# fpga1.net
KiCad netlist of a schematic drawn in Altium Designer
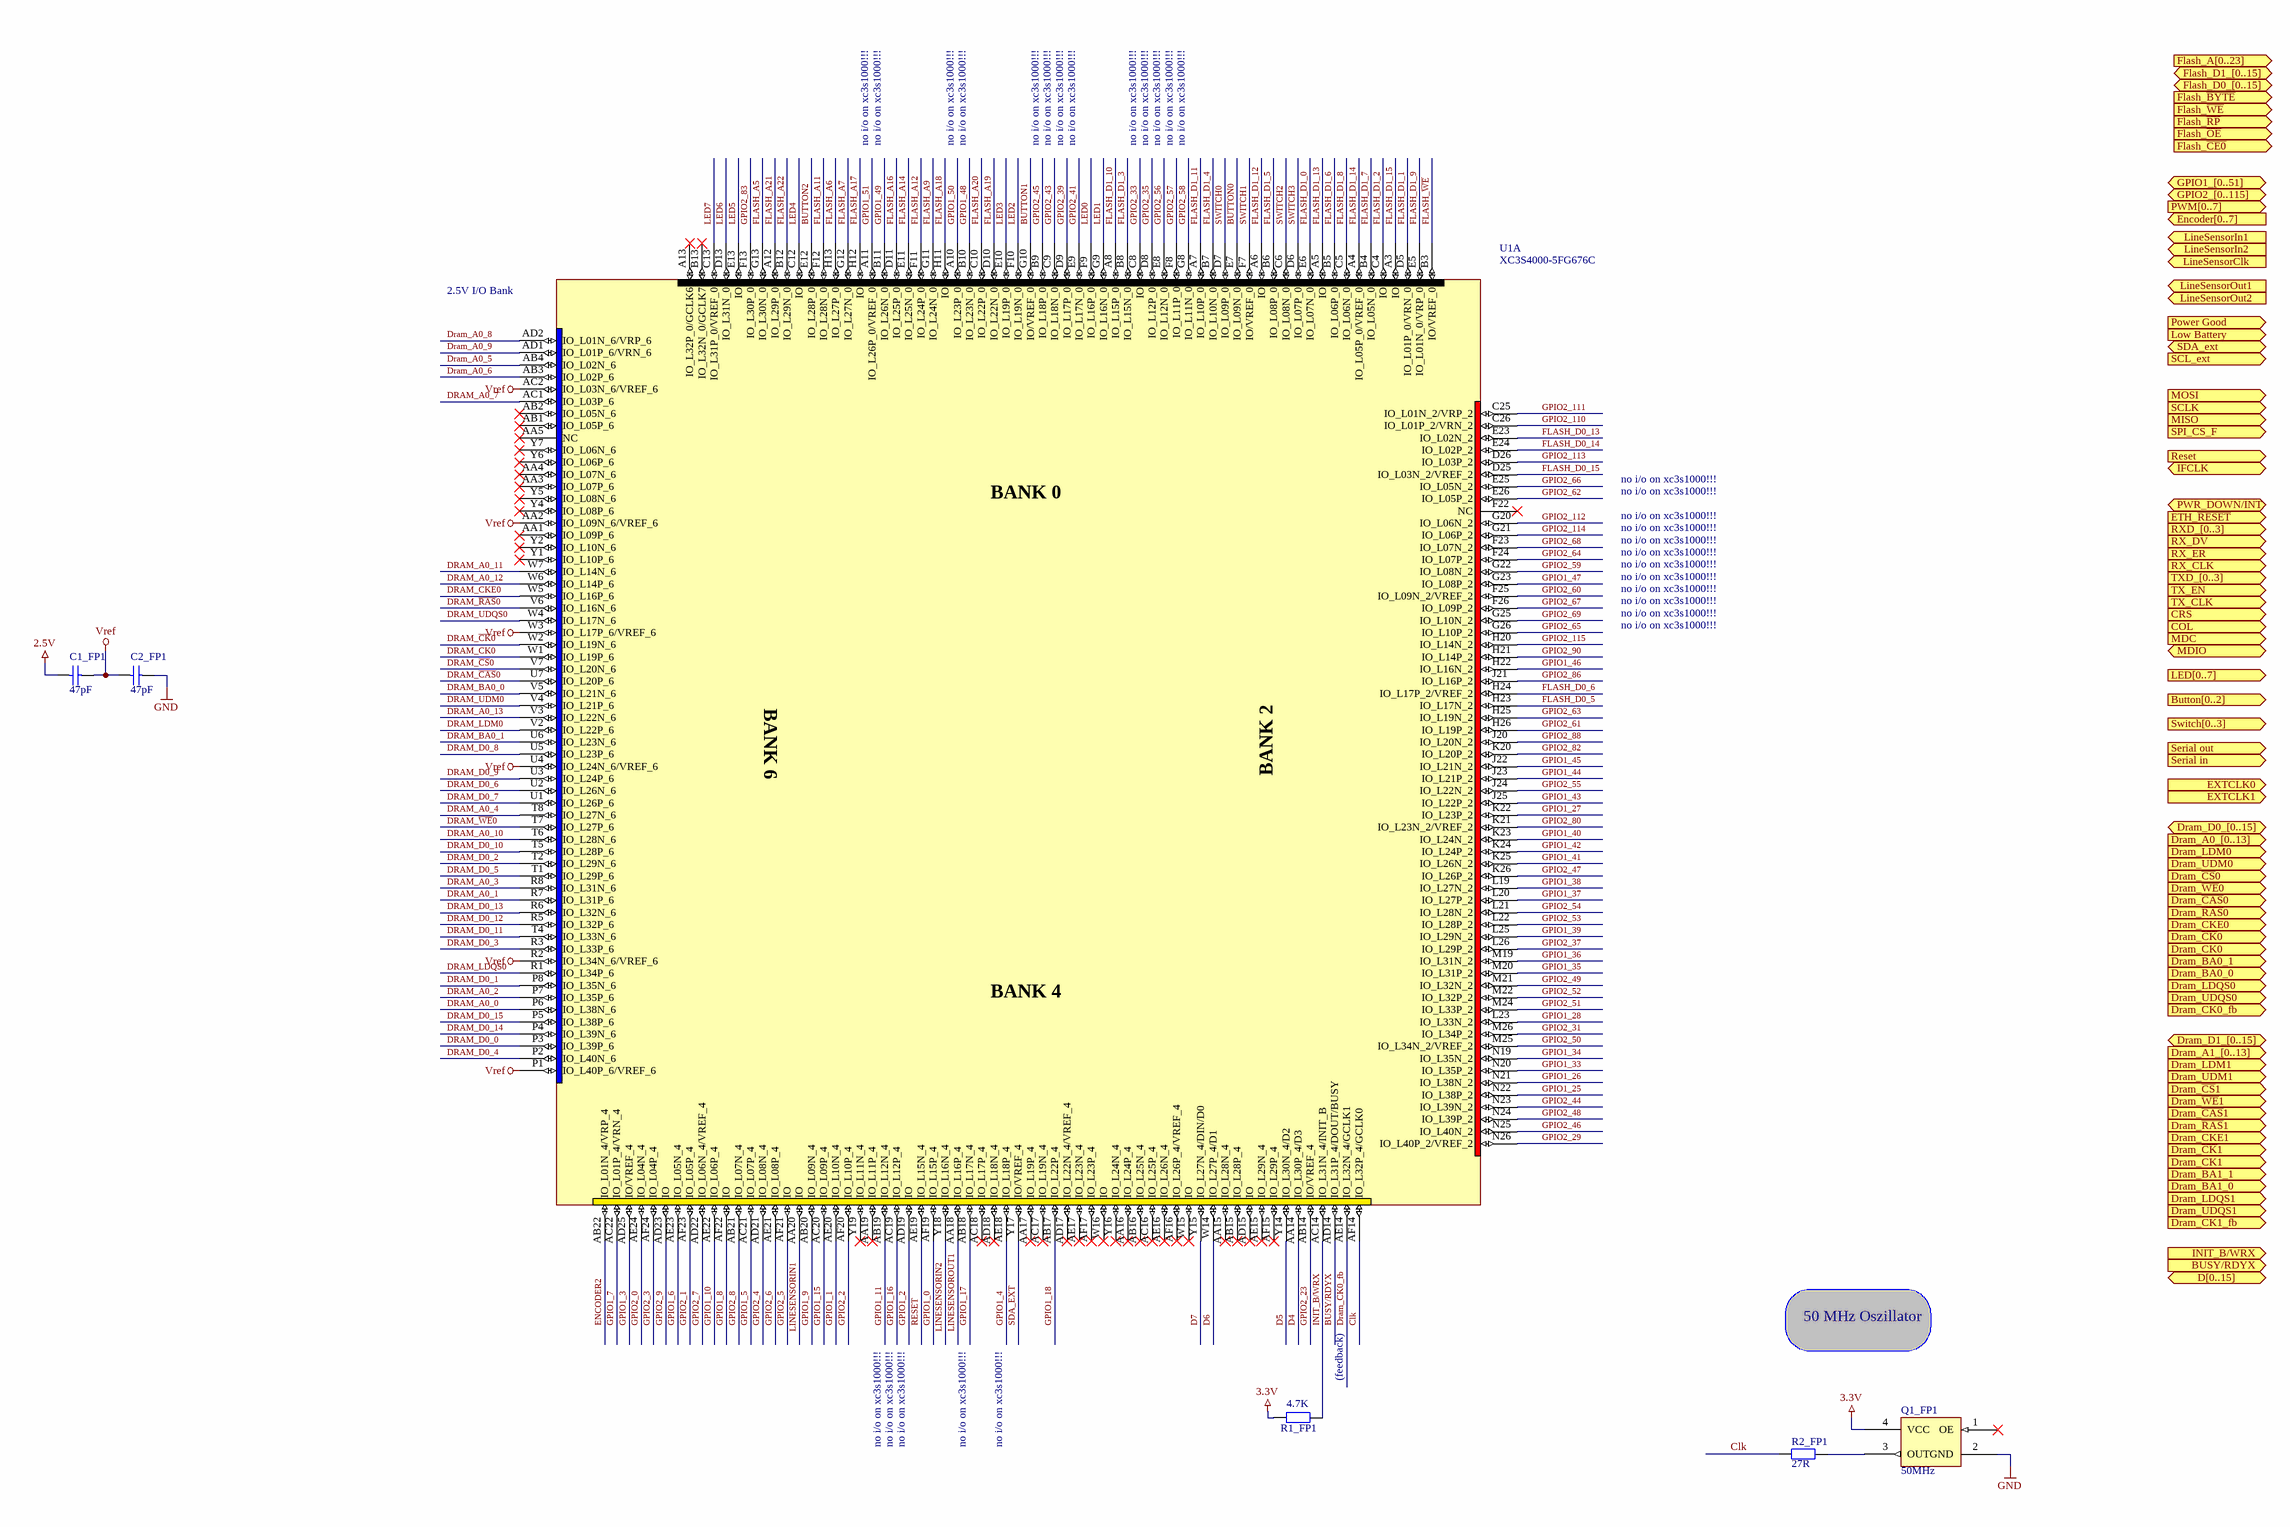
[diagram p0: fpga1.SchDoc]

(export (version "E")
  (design (tool "Eeschema 10.0.6"))
  (components
    (comp (ref "C1_FP1")
      (value "47pF")
      (footprint "0402")
      (description "Capacitor")
      (fields
        (field (name "MANUFACTURER") "Murata")
        (field (name "PART NUMBER") "GRM1555C1H470JZ01D")
        (field (name "PUBLISHER") "Altium Limited")
      )
      (libsource (lib "Miscellaneous Devices") (part "Cap"))
    )
    (comp (ref "C2_FP1")
      (value "47pF")
      (footprint "0402")
      (description "Capacitor")
      (fields
        (field (name "MANUFACTURER") "Murata")
        (field (name "PART NUMBER") "GRM1555C1H470JZ01D")
        (field (name "PUBLISHER") "Altium Limited")
      )
      (libsource (lib "Miscellaneous Devices") (part "Cap"))
    )
    (comp (ref "Q1_FP1")
      (value "50MHz")
      (footprint "SMD-VX3E")
      (description "TTL Quarz Oszillator")
      (fields (field (name "MANUFACTURER") "Jauch") (field (name "PART NUMBER") "VX3MH-5000"))
      (libsource (lib "CoolARM-Kit") (part "QUARZ_OSZI_SMD"))
    )
    (comp (ref "R1_FP1")
      (value "4.7K")
      (footprint "0402")
      (description "Resistor")
      (fields
        (field (name "MANUFACTURER") "PHYCOMP")
        (field (name "PART NUMBER") "232270674702")
        (field (name "PUBLISHER") "Altium Limited")
      )
      (libsource (lib "Miscellaneous Devices") (part "Res2"))
    )
    (comp (ref "R2_FP1")
      (value "27R")
      (footprint "0402")
      (description "Resistor")
      (fields
        (field (name "MANUFACTURER") "PHYCOMP")
        (field (name "PART NUMBER") "232270672709")
        (field (name "PUBLISHER") "Altium Limited")
      )
      (libsource (lib "Miscellaneous Devices") (part "Res2"))
    )
    (comp (ref "U1")
      (value "XC3S4000-5FG676C")
      (footprint "FG676")
      (description "Spartan-3 1.2V FPGA, 487 User I/Os, 676-ball FBGA, High Performance, Commercial Grade")
      (fields (field (name "MANUFACTURER") "Xilinx") (field (name "PUBLISHER") "Altium Limited"))
      (libsource (lib "gecko3-user") (part "XC3S1500-5FG676C"))
    )
  )
  (nets
    (net (code "228") (name "/BUSY{slash}RDYX") (class "Default")
      (node (ref "U1") (pin "AD14") (pinfunction "IO_L31P_4/DOUT/BUSY_AD14") (pintype "bidirectional"))
    )
    (net (code "229") (name "/BUTTON0") (class "Default")
      (node (ref "U1") (pin "E7") (pinfunction "IO_L09N_0_E7") (pintype "bidirectional"))
    )
    (net (code "230") (name "/BUTTON1") (class "Default")
      (node (ref "U1") (pin "G10") (pinfunction "IO/VREF_0_G10") (pintype "bidirectional"))
    )
    (net (code "231") (name "/BUTTON2") (class "Default")
      (node (ref "U1") (pin "E12") (pinfunction "IO_L28P_0_E12") (pintype "bidirectional"))
    )
    (net (code "235") (name "/Clk") (class "Default")
      (node (ref "R2_FP1") (pin "1") (pinfunction "1_1") (pintype "passive"))
      (node (ref "U1") (pin "AF14") (pinfunction "IO_L32P_4/GCLK0_AF14") (pintype "bidirectional"))
    )
    (net (code "236") (name "/D4") (class "Default")
      (node (ref "U1") (pin "AA14") (pinfunction "IO_L30P_4/D3_AA14") (pintype "bidirectional"))
    )
    (net (code "237") (name "/D5") (class "Default")
      (node (ref "U1") (pin "Y14") (pinfunction "IO_L30N_4/D2_Y14") (pintype "bidirectional"))
    )
    (net (code "238") (name "/D6") (class "Default")
      (node (ref "U1") (pin "W14") (pinfunction "IO_L27P_4/D1_W14") (pintype "bidirectional"))
    )
    (net (code "239") (name "/D7") (class "Default")
      (node (ref "U1") (pin "Y15") (pinfunction "IO_L27N_4/DIN/D0_Y15") (pintype "bidirectional"))
    )
    (net (code "240") (name "/DRAM_A0_0") (class "Default")
      (node (ref "U1") (pin "P6") (pinfunction "IO_L38N_6_P6") (pintype "bidirectional"))
    )
    (net (code "241") (name "/DRAM_A0_1") (class "Default")
      (node (ref "U1") (pin "R7") (pinfunction "IO_L31P_6_R7") (pintype "bidirectional"))
    )
    (net (code "242") (name "/DRAM_A0_2") (class "Default")
      (node (ref "U1") (pin "P7") (pinfunction "IO_L35P_6_P7") (pintype "bidirectional"))
    )
    (net (code "243") (name "/DRAM_A0_3") (class "Default")
      (node (ref "U1") (pin "R8") (pinfunction "IO_L31N_6_R8") (pintype "bidirectional"))
    )
    (net (code "244") (name "/DRAM_A0_4") (class "Default")
      (node (ref "U1") (pin "T8") (pinfunction "IO_L27N_6_T8") (pintype "bidirectional"))
    )
    (net (code "245") (name "/DRAM_A0_7") (class "Default")
      (node (ref "U1") (pin "AC1") (pinfunction "IO_L03P_6_AC1") (pintype "bidirectional"))
    )
    (net (code "246") (name "/DRAM_A0_10") (class "Default")
      (node (ref "U1") (pin "T6") (pinfunction "IO_L28N_6_T6") (pintype "bidirectional"))
    )
    (net (code "247") (name "/DRAM_A0_11") (class "Default")
      (node (ref "U1") (pin "W7") (pinfunction "IO_L14N_6_W7") (pintype "bidirectional"))
    )
    (net (code "248") (name "/DRAM_A0_12") (class "Default")
      (node (ref "U1") (pin "W6") (pinfunction "IO_L14P_6_W6") (pintype "bidirectional"))
    )
    (net (code "249") (name "/DRAM_A0_13") (class "Default")
      (node (ref "U1") (pin "V3") (pinfunction "IO_L22N_6_V3") (pintype "bidirectional"))
    )
    (net (code "250") (name "/DRAM_BA0_0") (class "Default")
      (node (ref "U1") (pin "V5") (pinfunction "IO_L21N_6_V5") (pintype "bidirectional"))
    )
    (net (code "251") (name "/DRAM_BA0_1") (class "Default")
      (node (ref "U1") (pin "U6") (pinfunction "IO_L23N_6_U6") (pintype "bidirectional"))
    )
    (net (code "252") (name "/DRAM_CK0") (class "Default")
      (node (ref "U1") (pin "W1") (pinfunction "IO_L19P_6_W1") (pintype "bidirectional"))
    )
    (net (code "253") (name "/DRAM_CKE0") (class "Default")
      (node (ref "U1") (pin "W5") (pinfunction "IO_L16P_6_W5") (pintype "bidirectional"))
    )
    (net (code "254") (name "/DRAM_D0_0") (class "Default")
      (node (ref "U1") (pin "P3") (pinfunction "IO_L39P_6_P3") (pintype "bidirectional"))
    )
    (net (code "255") (name "/DRAM_D0_1") (class "Default")
      (node (ref "U1") (pin "P8") (pinfunction "IO_L35N_6_P8") (pintype "bidirectional"))
    )
    (net (code "256") (name "/DRAM_D0_2") (class "Default")
      (node (ref "U1") (pin "T2") (pinfunction "IO_L29N_6_T2") (pintype "bidirectional"))
    )
    (net (code "257") (name "/DRAM_D0_3") (class "Default")
      (node (ref "U1") (pin "R3") (pinfunction "IO_L33P_6_R3") (pintype "bidirectional"))
    )
    (net (code "258") (name "/DRAM_D0_4") (class "Default")
      (node (ref "U1") (pin "P2") (pinfunction "IO_L40N_6_P2") (pintype "bidirectional"))
    )
    (net (code "259") (name "/DRAM_D0_5") (class "Default")
      (node (ref "U1") (pin "T1") (pinfunction "IO_L29P_6_T1") (pintype "bidirectional"))
    )
    (net (code "260") (name "/DRAM_D0_6") (class "Default")
      (node (ref "U1") (pin "U2") (pinfunction "IO_L26N_6_U2") (pintype "bidirectional"))
    )
    (net (code "261") (name "/DRAM_D0_7") (class "Default")
      (node (ref "U1") (pin "U1") (pinfunction "IO_L26P_6_U1") (pintype "bidirectional"))
    )
    (net (code "262") (name "/DRAM_D0_8") (class "Default")
      (node (ref "U1") (pin "U5") (pinfunction "IO_L23P_6_U5") (pintype "bidirectional"))
    )
    (net (code "263") (name "/DRAM_D0_9") (class "Default")
      (node (ref "U1") (pin "U3") (pinfunction "IO_L24P_6_U3") (pintype "bidirectional"))
    )
    (net (code "264") (name "/DRAM_D0_10") (class "Default")
      (node (ref "U1") (pin "T5") (pinfunction "IO_L28P_6_T5") (pintype "bidirectional"))
    )
    (net (code "265") (name "/DRAM_D0_11") (class "Default")
      (node (ref "U1") (pin "T4") (pinfunction "IO_L33N_6_T4") (pintype "bidirectional"))
    )
    (net (code "266") (name "/DRAM_D0_12") (class "Default")
      (node (ref "U1") (pin "R5") (pinfunction "IO_L32P_6_R5") (pintype "bidirectional"))
    )
    (net (code "267") (name "/DRAM_D0_13") (class "Default")
      (node (ref "U1") (pin "R6") (pinfunction "IO_L32N_6_R6") (pintype "bidirectional"))
    )
    (net (code "268") (name "/DRAM_D0_14") (class "Default")
      (node (ref "U1") (pin "P4") (pinfunction "IO_L39N_6_P4") (pintype "bidirectional"))
    )
    (net (code "269") (name "/DRAM_D0_15") (class "Default")
      (node (ref "U1") (pin "P5") (pinfunction "IO_L38P_6_P5") (pintype "bidirectional"))
    )
    (net (code "270") (name "/DRAM_LDM0") (class "Default")
      (node (ref "U1") (pin "V2") (pinfunction "IO_L22P_6_V2") (pintype "bidirectional"))
    )
    (net (code "271") (name "/DRAM_LDQS0") (class "Default")
      (node (ref "U1") (pin "R1") (pinfunction "IO_L34P_6_R1") (pintype "bidirectional"))
    )
    (net (code "272") (name "/DRAM_UDM0") (class "Default")
      (node (ref "U1") (pin "V4") (pinfunction "IO_L21P_6_V4") (pintype "bidirectional"))
    )
    (net (code "273") (name "/DRAM_UDQS0") (class "Default")
      (node (ref "U1") (pin "W4") (pinfunction "IO_L17N_6_W4") (pintype "bidirectional"))
    )
    (net (code "274") (name "/DRAM_~{CAS}0") (class "Default")
      (node (ref "U1") (pin "U7") (pinfunction "IO_L20P_6_U7") (pintype "bidirectional"))
    )
    (net (code "275") (name "/DRAM_~{CK}0") (class "Default")
      (node (ref "U1") (pin "W2") (pinfunction "IO_L19N_6_W2") (pintype "bidirectional"))
    )
    (net (code "276") (name "/DRAM_~{CS}0") (class "Default")
      (node (ref "U1") (pin "V7") (pinfunction "IO_L20N_6_V7") (pintype "bidirectional"))
    )
    (net (code "277") (name "/DRAM_~{RAS}0") (class "Default")
      (node (ref "U1") (pin "V6") (pinfunction "IO_L16N_6_V6") (pintype "bidirectional"))
    )
    (net (code "278") (name "/DRAM_~{WE}0") (class "Default")
      (node (ref "U1") (pin "T7") (pinfunction "IO_L27P_6_T7") (pintype "bidirectional"))
    )
    (net (code "280") (name "/Dram_A0_5") (class "Default")
      (node (ref "U1") (pin "AB4") (pinfunction "IO_L02N_6_AB4") (pintype "bidirectional"))
    )
    (net (code "281") (name "/Dram_A0_6") (class "Default")
      (node (ref "U1") (pin "AB3") (pinfunction "IO_L02P_6_AB3") (pintype "bidirectional"))
    )
    (net (code "282") (name "/Dram_A0_8") (class "Default")
      (node (ref "U1") (pin "AD2") (pinfunction "IO_L01N_6/VRP_6_AD2") (pintype "bidirectional"))
    )
    (net (code "283") (name "/Dram_A0_9") (class "Default")
      (node (ref "U1") (pin "AD1") (pinfunction "IO_L01P_6/VRN_6_AD1") (pintype "bidirectional"))
    )
    (net (code "291") (name "/Dram_CK0_fb") (class "Default")
      (node (ref "U1") (pin "AE14") (pinfunction "IO_L32N_4/GCLK1_AE14") (pintype "bidirectional"))
    )
    (net (code "316") (name "/ENCODER2") (class "Default")
      (node (ref "U1") (pin "AB22") (pinfunction "IO_L01N_4/VRP_4_AB22") (pintype "bidirectional"))
    )
    (net (code "321") (name "/FLASH_A5") (class "Default")
      (node (ref "U1") (pin "G13") (pinfunction "IO_L30N_0_G13") (pintype "bidirectional"))
    )
    (net (code "322") (name "/FLASH_A6") (class "Default")
      (node (ref "U1") (pin "H13") (pinfunction "IO_L27P_0_H13") (pintype "bidirectional"))
    )
    (net (code "323") (name "/FLASH_A7") (class "Default")
      (node (ref "U1") (pin "G12") (pinfunction "IO_L27N_0_G12") (pintype "bidirectional"))
    )
    (net (code "324") (name "/FLASH_A9") (class "Default")
      (node (ref "U1") (pin "G11") (pinfunction "IO_L24N_0_G11") (pintype "bidirectional"))
    )
    (net (code "325") (name "/FLASH_A11") (class "Default")
      (node (ref "U1") (pin "F12") (pinfunction "IO_L28N_0_F12") (pintype "bidirectional"))
    )
    (net (code "326") (name "/FLASH_A12") (class "Default")
      (node (ref "U1") (pin "F11") (pinfunction "IO_L24P_0_F11") (pintype "bidirectional"))
    )
    (net (code "327") (name "/FLASH_A14") (class "Default")
      (node (ref "U1") (pin "E11") (pinfunction "IO_L25N_0_E11") (pintype "bidirectional"))
    )
    (net (code "328") (name "/FLASH_A16") (class "Default")
      (node (ref "U1") (pin "D11") (pinfunction "IO_L25P_0_D11") (pintype "bidirectional"))
    )
    (net (code "329") (name "/FLASH_A17") (class "Default")
      (node (ref "U1") (pin "H12") (pinfunction "IO_H12") (pintype "bidirectional"))
    )
    (net (code "330") (name "/FLASH_A18") (class "Default")
      (node (ref "U1") (pin "H11") (pinfunction "IO_H11") (pintype "bidirectional"))
    )
    (net (code "331") (name "/FLASH_A19") (class "Default")
      (node (ref "U1") (pin "D10") (pinfunction "IO_L22N_0_D10") (pintype "bidirectional"))
    )
    (net (code "332") (name "/FLASH_A20") (class "Default")
      (node (ref "U1") (pin "C10") (pinfunction "IO_L22P_0_C10") (pintype "bidirectional"))
    )
    (net (code "333") (name "/FLASH_A21") (class "Default")
      (node (ref "U1") (pin "A12") (pinfunction "IO_L29P_0_A12") (pintype "bidirectional"))
    )
    (net (code "334") (name "/FLASH_A22") (class "Default")
      (node (ref "U1") (pin "B12") (pinfunction "IO_L29N_0_B12") (pintype "bidirectional"))
    )
    (net (code "335") (name "/FLASH_D0_5") (class "Default")
      (node (ref "U1") (pin "H23") (pinfunction "IO_L17N_2_H23") (pintype "bidirectional"))
    )
    (net (code "336") (name "/FLASH_D0_6") (class "Default")
      (node (ref "U1") (pin "H24") (pinfunction "IO_L17P_2/VREF_2_H24") (pintype "bidirectional"))
    )
    (net (code "337") (name "/FLASH_D0_13") (class "Default")
      (node (ref "U1") (pin "E23") (pinfunction "IO_L02N_2_E23") (pintype "bidirectional"))
    )
    (net (code "338") (name "/FLASH_D0_14") (class "Default")
      (node (ref "U1") (pin "E24") (pinfunction "IO_L02P_2_E24") (pintype "bidirectional"))
    )
    (net (code "339") (name "/FLASH_D0_15") (class "Default")
      (node (ref "U1") (pin "D25") (pinfunction "IO_L03N_2/VREF_2_D25") (pintype "bidirectional"))
    )
    (net (code "340") (name "/FLASH_D1_0") (class "Default")
      (node (ref "U1") (pin "E6") (pinfunction "IO_L07N_0_E6") (pintype "bidirectional"))
    )
    (net (code "341") (name "/FLASH_D1_1") (class "Default")
      (node (ref "U1") (pin "D5") (pinfunction "IO_L01P_0/VRN_0_D5") (pintype "bidirectional"))
    )
    (net (code "342") (name "/FLASH_D1_2") (class "Default")
      (node (ref "U1") (pin "C4") (pinfunction "IO_C4") (pintype "bidirectional"))
    )
    (net (code "343") (name "/FLASH_D1_3") (class "Default")
      (node (ref "U1") (pin "B8") (pinfunction "IO_L15N_0_B8") (pintype "bidirectional"))
    )
    (net (code "344") (name "/FLASH_D1_4") (class "Default")
      (node (ref "U1") (pin "B7") (pinfunction "IO_L10N_0_B7") (pintype "bidirectional"))
    )
    (net (code "345") (name "/FLASH_D1_5") (class "Default")
      (node (ref "U1") (pin "B6") (pinfunction "IO_L08P_0_B6") (pintype "bidirectional"))
    )
    (net (code "346") (name "/FLASH_D1_6") (class "Default")
      (node (ref "U1") (pin "B5") (pinfunction "IO_L06P_0_B5") (pintype "bidirectional"))
    )
    (net (code "347") (name "/FLASH_D1_7") (class "Default")
      (node (ref "U1") (pin "B4") (pinfunction "IO_L05N_0_B4") (pintype "bidirectional"))
    )
    (net (code "348") (name "/FLASH_D1_8") (class "Default")
      (node (ref "U1") (pin "C5") (pinfunction "IO_L06N_0_C5") (pintype "bidirectional"))
    )
    (net (code "349") (name "/FLASH_D1_9") (class "Default")
      (node (ref "U1") (pin "E5") (pinfunction "IO_L01N_0/VRP_0_E5") (pintype "bidirectional"))
    )
    (net (code "350") (name "/FLASH_D1_10") (class "Default")
      (node (ref "U1") (pin "A8") (pinfunction "IO_L15P_0_A8") (pintype "bidirectional"))
    )
    (net (code "351") (name "/FLASH_D1_11") (class "Default")
      (node (ref "U1") (pin "A7") (pinfunction "IO_L10P_0_A7") (pintype "bidirectional"))
    )
    (net (code "352") (name "/FLASH_D1_12") (class "Default")
      (node (ref "U1") (pin "A6") (pinfunction "IO_A6") (pintype "bidirectional"))
    )
    (net (code "353") (name "/FLASH_D1_13") (class "Default")
      (node (ref "U1") (pin "A5") (pinfunction "IO_A5") (pintype "bidirectional"))
    )
    (net (code "354") (name "/FLASH_D1_14") (class "Default")
      (node (ref "U1") (pin "A4") (pinfunction "IO_L05P_0/VREF_0_A4") (pintype "bidirectional"))
    )
    (net (code "355") (name "/FLASH_D1_15") (class "Default")
      (node (ref "U1") (pin "A3") (pinfunction "IO_A3") (pintype "bidirectional"))
    )
    (net (code "356") (name "/FLASH_~{WE}") (class "Default")
      (node (ref "U1") (pin "B3") (pinfunction "IO/VREF_0_B3") (pintype "bidirectional"))
    )
    (net (code "365") (name "/GPIO1_0") (class "Default")
      (node (ref "U1") (pin "AF19") (pinfunction "IO_L15P_4_AF19") (pintype "bidirectional"))
    )
    (net (code "366") (name "/GPIO1_1") (class "Default")
      (node (ref "U1") (pin "AE20") (pinfunction "IO_L10N_4_AE20") (pintype "bidirectional"))
    )
    (net (code "367") (name "/GPIO1_2") (class "Default")
      (node (ref "U1") (pin "AD19") (pinfunction "IO_AD19") (pintype "bidirectional"))
    )
    (net (code "368") (name "/GPIO1_3") (class "Default")
      (node (ref "U1") (pin "AD25") (pinfunction "IO/VREF_4_AD25") (pintype "bidirectional"))
    )
    (net (code "369") (name "/GPIO1_4") (class "Default")
      (node (ref "U1") (pin "AE18") (pinfunction "IO_L18P_4_AE18") (pintype "bidirectional"))
    )
    (net (code "370") (name "/GPIO1_5") (class "Default")
      (node (ref "U1") (pin "AC21") (pinfunction "IO_L07P_4_AC21") (pintype "bidirectional"))
    )
    (net (code "371") (name "/GPIO1_6") (class "Default")
      (node (ref "U1") (pin "AE23") (pinfunction "IO_L05N_4_AE23") (pintype "bidirectional"))
    )
    (net (code "372") (name "/GPIO1_7") (class "Default")
      (node (ref "U1") (pin "AC22") (pinfunction "IO_L01P_4/VRN_4_AC22") (pintype "bidirectional"))
    )
    (net (code "373") (name "/GPIO1_8") (class "Default")
      (node (ref "U1") (pin "AF22") (pinfunction "IO_AF22") (pintype "bidirectional"))
    )
    (net (code "374") (name "/GPIO1_9") (class "Default")
      (node (ref "U1") (pin "AB20") (pinfunction "IO_L09N_4_AB20") (pintype "bidirectional"))
    )
    (net (code "375") (name "/GPIO1_10") (class "Default")
      (node (ref "U1") (pin "AE22") (pinfunction "IO_L06P_4_AE22") (pintype "bidirectional"))
    )
    (net (code "376") (name "/GPIO1_11") (class "Default")
      (node (ref "U1") (pin "AB19") (pinfunction "IO_L12N_4_AB19") (pintype "bidirectional"))
    )
    (net (code "377") (name "/GPIO1_15") (class "Default")
      (node (ref "U1") (pin "AC20") (pinfunction "IO_L09P_4_AC20") (pintype "bidirectional"))
    )
    (net (code "378") (name "/GPIO1_16") (class "Default")
      (node (ref "U1") (pin "AC19") (pinfunction "IO_L12P_4_AC19") (pintype "bidirectional"))
    )
    (net (code "379") (name "/GPIO1_17") (class "Default")
      (node (ref "U1") (pin "AB18") (pinfunction "IO_L17N_4_AB18") (pintype "bidirectional"))
    )
    (net (code "380") (name "/GPIO1_18") (class "Default")
      (node (ref "U1") (pin "AB17") (pinfunction "IO_L22P_4_AB17") (pintype "bidirectional"))
    )
    (net (code "381") (name "/GPIO1_25") (class "Default")
      (node (ref "U1") (pin "N22") (pinfunction "IO_L38P_2_N22") (pintype "bidirectional"))
    )
    (net (code "382") (name "/GPIO1_26") (class "Default")
      (node (ref "U1") (pin "N21") (pinfunction "IO_L38N_2_N21") (pintype "bidirectional"))
    )
    (net (code "383") (name "/GPIO1_27") (class "Default")
      (node (ref "U1") (pin "K22") (pinfunction "IO_L23P_2_K22") (pintype "bidirectional"))
    )
    (net (code "384") (name "/GPIO1_28") (class "Default")
      (node (ref "U1") (pin "L23") (pinfunction "IO_L33N_2_L23") (pintype "bidirectional"))
    )
    (net (code "385") (name "/GPIO1_33") (class "Default")
      (node (ref "U1") (pin "N20") (pinfunction "IO_L35P_2_N20") (pintype "bidirectional"))
    )
    (net (code "386") (name "/GPIO1_34") (class "Default")
      (node (ref "U1") (pin "N19") (pinfunction "IO_L35N_2_N19") (pintype "bidirectional"))
    )
    (net (code "387") (name "/GPIO1_35") (class "Default")
      (node (ref "U1") (pin "M20") (pinfunction "IO_L31P_2_M20") (pintype "bidirectional"))
    )
    (net (code "388") (name "/GPIO1_36") (class "Default")
      (node (ref "U1") (pin "M19") (pinfunction "IO_L31N_2_M19") (pintype "bidirectional"))
    )
    (net (code "389") (name "/GPIO1_37") (class "Default")
      (node (ref "U1") (pin "L20") (pinfunction "IO_L27P_2_L20") (pintype "bidirectional"))
    )
    (net (code "390") (name "/GPIO1_38") (class "Default")
      (node (ref "U1") (pin "L19") (pinfunction "IO_L27N_2_L19") (pintype "bidirectional"))
    )
    (net (code "391") (name "/GPIO1_39") (class "Default")
      (node (ref "U1") (pin "L25") (pinfunction "IO_L29N_2_L25") (pintype "bidirectional"))
    )
    (net (code "392") (name "/GPIO1_40") (class "Default")
      (node (ref "U1") (pin "K23") (pinfunction "IO_L24N_2_K23") (pintype "bidirectional"))
    )
    (net (code "393") (name "/GPIO1_41") (class "Default")
      (node (ref "U1") (pin "K25") (pinfunction "IO_L26N_2_K25") (pintype "bidirectional"))
    )
    (net (code "394") (name "/GPIO1_42") (class "Default")
      (node (ref "U1") (pin "K24") (pinfunction "IO_L24P_2_K24") (pintype "bidirectional"))
    )
    (net (code "395") (name "/GPIO1_43") (class "Default")
      (node (ref "U1") (pin "J25") (pinfunction "IO_L22P_2_J25") (pintype "bidirectional"))
    )
    (net (code "396") (name "/GPIO1_44") (class "Default")
      (node (ref "U1") (pin "J23") (pinfunction "IO_L21P_2_J23") (pintype "bidirectional"))
    )
    (net (code "397") (name "/GPIO1_45") (class "Default")
      (node (ref "U1") (pin "J22") (pinfunction "IO_L21N_2_J22") (pintype "bidirectional"))
    )
    (net (code "398") (name "/GPIO1_46") (class "Default")
      (node (ref "U1") (pin "H22") (pinfunction "IO_L16N_2_H22") (pintype "bidirectional"))
    )
    (net (code "399") (name "/GPIO1_47") (class "Default")
      (node (ref "U1") (pin "G23") (pinfunction "IO_L08P_2_G23") (pintype "bidirectional"))
    )
    (net (code "400") (name "/GPIO1_48") (class "Default")
      (node (ref "U1") (pin "B10") (pinfunction "IO_L23N_0_B10") (pintype "bidirectional"))
    )
    (net (code "401") (name "/GPIO1_49") (class "Default")
      (node (ref "U1") (pin "B11") (pinfunction "IO_L26N_0_B11") (pintype "bidirectional"))
    )
    (net (code "402") (name "/GPIO1_50") (class "Default")
      (node (ref "U1") (pin "A10") (pinfunction "IO_L23P_0_A10") (pintype "bidirectional"))
    )
    (net (code "403") (name "/GPIO1_51") (class "Default")
      (node (ref "U1") (pin "A11") (pinfunction "IO_L26P_0/VREF_0_A11") (pintype "bidirectional"))
    )
    (net (code "405") (name "/GPIO2_0") (class "Default")
      (node (ref "U1") (pin "AE24") (pinfunction "IO_L04N_4_AE24") (pintype "bidirectional"))
    )
    (net (code "406") (name "/GPIO2_1") (class "Default")
      (node (ref "U1") (pin "AF23") (pinfunction "IO_L05P_4_AF23") (pintype "bidirectional"))
    )
    (net (code "407") (name "/GPIO2_2") (class "Default")
      (node (ref "U1") (pin "AF20") (pinfunction "IO_L10P_4_AF20") (pintype "bidirectional"))
    )
    (net (code "408") (name "/GPIO2_3") (class "Default")
      (node (ref "U1") (pin "AF24") (pinfunction "IO_L04P_4_AF24") (pintype "bidirectional"))
    )
    (net (code "409") (name "/GPIO2_4") (class "Default")
      (node (ref "U1") (pin "AD21") (pinfunction "IO_L08N_4_AD21") (pintype "bidirectional"))
    )
    (net (code "410") (name "/GPIO2_5") (class "Default")
      (node (ref "U1") (pin "AF21") (pinfunction "IO_AF21") (pintype "bidirectional"))
    )
    (net (code "411") (name "/GPIO2_6") (class "Default")
      (node (ref "U1") (pin "AE21") (pinfunction "IO_L08P_4_AE21") (pintype "bidirectional"))
    )
    (net (code "412") (name "/GPIO2_7") (class "Default")
      (node (ref "U1") (pin "AD22") (pinfunction "IO_L06N_4/VREF_4_AD22") (pintype "bidirectional"))
    )
    (net (code "413") (name "/GPIO2_8") (class "Default")
      (node (ref "U1") (pin "AB21") (pinfunction "IO_L07N_4_AB21") (pintype "bidirectional"))
    )
    (net (code "414") (name "/GPIO2_9") (class "Default")
      (node (ref "U1") (pin "AD23") (pinfunction "IO_AD23") (pintype "bidirectional"))
    )
    (net (code "415") (name "/GPIO2_23") (class "Default")
      (node (ref "U1") (pin "AB14") (pinfunction "IO/VREF_4_AB14") (pintype "bidirectional"))
    )
    (net (code "416") (name "/GPIO2_29") (class "Default")
      (node (ref "U1") (pin "N26") (pinfunction "IO_L40P_2/VREF_2_N26") (pintype "bidirectional"))
    )
    (net (code "417") (name "/GPIO2_31") (class "Default")
      (node (ref "U1") (pin "M26") (pinfunction "IO_L34P_2_M26") (pintype "bidirectional"))
    )
    (net (code "418") (name "/GPIO2_33") (class "Default")
      (node (ref "U1") (pin "C8") (pinfunction "IO_C8") (pintype "bidirectional"))
    )
    (net (code "419") (name "/GPIO2_35") (class "Default")
      (node (ref "U1") (pin "D8") (pinfunction "IO_L12P_0_D8") (pintype "bidirectional"))
    )
    (net (code "420") (name "/GPIO2_37") (class "Default")
      (node (ref "U1") (pin "L26") (pinfunction "IO_L29P_2_L26") (pintype "bidirectional"))
    )
    (net (code "421") (name "/GPIO2_39") (class "Default")
      (node (ref "U1") (pin "D9") (pinfunction "IO_L17P_0_D9") (pintype "bidirectional"))
    )
    (net (code "422") (name "/GPIO2_41") (class "Default")
      (node (ref "U1") (pin "E9") (pinfunction "IO_L17N_0_E9") (pintype "bidirectional"))
    )
    (net (code "423") (name "/GPIO2_43") (class "Default")
      (node (ref "U1") (pin "C9") (pinfunction "IO_L18N_0_C9") (pintype "bidirectional"))
    )
    (net (code "424") (name "/GPIO2_44") (class "Default")
      (node (ref "U1") (pin "N23") (pinfunction "IO_L39N_2_N23") (pintype "bidirectional"))
    )
    (net (code "425") (name "/GPIO2_45") (class "Default")
      (node (ref "U1") (pin "B9") (pinfunction "IO_L18P_0_B9") (pintype "bidirectional"))
    )
    (net (code "426") (name "/GPIO2_46") (class "Default")
      (node (ref "U1") (pin "N25") (pinfunction "IO_L40N_2_N25") (pintype "bidirectional"))
    )
    (net (code "427") (name "/GPIO2_47") (class "Default")
      (node (ref "U1") (pin "K26") (pinfunction "IO_L26P_2_K26") (pintype "bidirectional"))
    )
    (net (code "428") (name "/GPIO2_48") (class "Default")
      (node (ref "U1") (pin "N24") (pinfunction "IO_L39P_2_N24") (pintype "bidirectional"))
    )
    (net (code "429") (name "/GPIO2_49") (class "Default")
      (node (ref "U1") (pin "M21") (pinfunction "IO_L32N_2_M21") (pintype "bidirectional"))
    )
    (net (code "430") (name "/GPIO2_50") (class "Default")
      (node (ref "U1") (pin "M25") (pinfunction "IO_L34N_2/VREF_2_M25") (pintype "bidirectional"))
    )
    (net (code "431") (name "/GPIO2_51") (class "Default")
      (node (ref "U1") (pin "M24") (pinfunction "IO_L33P_2_M24") (pintype "bidirectional"))
    )
    (net (code "432") (name "/GPIO2_52") (class "Default")
      (node (ref "U1") (pin "M22") (pinfunction "IO_L32P_2_M22") (pintype "bidirectional"))
    )
    (net (code "433") (name "/GPIO2_53") (class "Default")
      (node (ref "U1") (pin "L22") (pinfunction "IO_L28P_2_L22") (pintype "bidirectional"))
    )
    (net (code "434") (name "/GPIO2_54") (class "Default")
      (node (ref "U1") (pin "L21") (pinfunction "IO_L28N_2_L21") (pintype "bidirectional"))
    )
    (net (code "435") (name "/GPIO2_55") (class "Default")
      (node (ref "U1") (pin "J24") (pinfunction "IO_L22N_2_J24") (pintype "bidirectional"))
    )
    (net (code "436") (name "/GPIO2_56") (class "Default")
      (node (ref "U1") (pin "E8") (pinfunction "IO_L12N_0_E8") (pintype "bidirectional"))
    )
    (net (code "437") (name "/GPIO2_57") (class "Default")
      (node (ref "U1") (pin "F8") (pinfunction "IO_L11P_0_F8") (pintype "bidirectional"))
    )
    (net (code "438") (name "/GPIO2_58") (class "Default")
      (node (ref "U1") (pin "G8") (pinfunction "IO_L11N_0_G8") (pintype "bidirectional"))
    )
    (net (code "439") (name "/GPIO2_59") (class "Default")
      (node (ref "U1") (pin "G22") (pinfunction "IO_L08N_2_G22") (pintype "bidirectional"))
    )
    (net (code "440") (name "/GPIO2_60") (class "Default")
      (node (ref "U1") (pin "F25") (pinfunction "IO_L09N_2/VREF_2_F25") (pintype "bidirectional"))
    )
    (net (code "441") (name "/GPIO2_61") (class "Default")
      (node (ref "U1") (pin "H26") (pinfunction "IO_L19P_2_H26") (pintype "bidirectional"))
    )
    (net (code "442") (name "/GPIO2_62") (class "Default")
      (node (ref "U1") (pin "E26") (pinfunction "IO_L05P_2_E26") (pintype "bidirectional"))
    )
    (net (code "443") (name "/GPIO2_63") (class "Default")
      (node (ref "U1") (pin "H25") (pinfunction "IO_L19N_2_H25") (pintype "bidirectional"))
    )
    (net (code "444") (name "/GPIO2_64") (class "Default")
      (node (ref "U1") (pin "F24") (pinfunction "IO_L07P_2_F24") (pintype "bidirectional"))
    )
    (net (code "445") (name "/GPIO2_65") (class "Default")
      (node (ref "U1") (pin "G26") (pinfunction "IO_L10P_2_G26") (pintype "bidirectional"))
    )
    (net (code "446") (name "/GPIO2_66") (class "Default")
      (node (ref "U1") (pin "E25") (pinfunction "IO_L05N_2_E25") (pintype "bidirectional"))
    )
    (net (code "447") (name "/GPIO2_67") (class "Default")
      (node (ref "U1") (pin "F26") (pinfunction "IO_L09P_2_F26") (pintype "bidirectional"))
    )
    (net (code "448") (name "/GPIO2_68") (class "Default")
      (node (ref "U1") (pin "F23") (pinfunction "IO_L07N_2_F23") (pintype "bidirectional"))
    )
    (net (code "449") (name "/GPIO2_69") (class "Default")
      (node (ref "U1") (pin "G25") (pinfunction "IO_L10N_2_G25") (pintype "bidirectional"))
    )
    (net (code "450") (name "/GPIO2_80") (class "Default")
      (node (ref "U1") (pin "K21") (pinfunction "IO_L23N_2/VREF_2_K21") (pintype "bidirectional"))
    )
    (net (code "451") (name "/GPIO2_82") (class "Default")
      (node (ref "U1") (pin "K20") (pinfunction "IO_L20P_2_K20") (pintype "bidirectional"))
    )
    (net (code "452") (name "/GPIO2_83") (class "Default")
      (node (ref "U1") (pin "F13") (pinfunction "IO_L30P_0_F13") (pintype "bidirectional"))
    )
    (net (code "453") (name "/GPIO2_86") (class "Default")
      (node (ref "U1") (pin "J21") (pinfunction "IO_L16P_2_J21") (pintype "bidirectional"))
    )
    (net (code "454") (name "/GPIO2_88") (class "Default")
      (node (ref "U1") (pin "J20") (pinfunction "IO_L20N_2_J20") (pintype "bidirectional"))
    )
    (net (code "455") (name "/GPIO2_90") (class "Default")
      (node (ref "U1") (pin "H21") (pinfunction "IO_L14P_2_H21") (pintype "bidirectional"))
    )
    (net (code "456") (name "/GPIO2_110") (class "Default")
      (node (ref "U1") (pin "C26") (pinfunction "IO_L01P_2/VRN_2_C26") (pintype "bidirectional"))
    )
    (net (code "457") (name "/GPIO2_111") (class "Default")
      (node (ref "U1") (pin "C25") (pinfunction "IO_L01N_2/VRP_2_C25") (pintype "bidirectional"))
    )
    (net (code "458") (name "/GPIO2_112") (class "Default")
      (node (ref "U1") (pin "G20") (pinfunction "IO_L06N_2_G20") (pintype "bidirectional"))
    )
    (net (code "459") (name "/GPIO2_113") (class "Default")
      (node (ref "U1") (pin "D26") (pinfunction "IO_L03P_2_D26") (pintype "bidirectional"))
    )
    (net (code "460") (name "/GPIO2_114") (class "Default")
      (node (ref "U1") (pin "G21") (pinfunction "IO_L06P_2_G21") (pintype "bidirectional"))
    )
    (net (code "461") (name "/GPIO2_115") (class "Default")
      (node (ref "U1") (pin "H20") (pinfunction "IO_L14N_2_H20") (pintype "bidirectional"))
    )
    (net (code "464") (name "/INIT_B{slash}WRX") (class "Default")
      (node (ref "R1_FP1") (pin "2") (pinfunction "2_2") (pintype "passive"))
      (node (ref "U1") (pin "AC14") (pinfunction "IO_L31N_4/INIT_B_AC14") (pintype "bidirectional"))
    )
    (net (code "465") (name "/LED0") (class "Default")
      (node (ref "U1") (pin "F9") (pinfunction "IO_L16P_0_F9") (pintype "bidirectional"))
    )
    (net (code "466") (name "/LED1") (class "Default")
      (node (ref "U1") (pin "G9") (pinfunction "IO_L16N_0_G9") (pintype "bidirectional"))
    )
    (net (code "467") (name "/LED2") (class "Default")
      (node (ref "U1") (pin "F10") (pinfunction "IO_L19N_0_F10") (pintype "bidirectional"))
    )
    (net (code "468") (name "/LED3") (class "Default")
      (node (ref "U1") (pin "E10") (pinfunction "IO_L19P_0_E10") (pintype "bidirectional"))
    )
    (net (code "469") (name "/LED4") (class "Default")
      (node (ref "U1") (pin "C12") (pinfunction "IO_C12") (pintype "bidirectional"))
    )
    (net (code "470") (name "/LED5") (class "Default")
      (node (ref "U1") (pin "E13") (pinfunction "IO_E13") (pintype "bidirectional"))
    )
    (net (code "471") (name "/LED6") (class "Default")
      (node (ref "U1") (pin "D13") (pinfunction "IO_L31N_0_D13") (pintype "bidirectional"))
    )
    (net (code "472") (name "/LED7") (class "Default")
      (node (ref "U1") (pin "C13") (pinfunction "IO_L31P_0/VREF_0_C13") (pintype "bidirectional"))
    )
    (net (code "474") (name "/LINESENSORIN1") (class "Default")
      (node (ref "U1") (pin "AA20") (pinfunction "IO_AA20") (pintype "bidirectional"))
    )
    (net (code "475") (name "/LINESENSORIN2") (class "Default")
      (node (ref "U1") (pin "Y18") (pinfunction "IO_L16N_4_Y18") (pintype "bidirectional"))
    )
    (net (code "476") (name "/LINESENSOROUT1") (class "Default")
      (node (ref "U1") (pin "AA18") (pinfunction "IO_L16P_4_AA18") (pintype "bidirectional"))
    )
    (net (code "490") (name "/RESET") (class "Default")
      (node (ref "U1") (pin "AE19") (pinfunction "IO_L15N_4_AE19") (pintype "bidirectional"))
    )
    (net (code "498") (name "/SDA_EXT") (class "Default")
      (node (ref "U1") (pin "Y17") (pinfunction "IO/VREF_4_Y17") (pintype "bidirectional"))
    )
    (net (code "501") (name "/SWITCH0") (class "Default")
      (node (ref "U1") (pin "D7") (pinfunction "IO_L09P_0_D7") (pintype "bidirectional"))
    )
    (net (code "502") (name "/SWITCH1") (class "Default")
      (node (ref "U1") (pin "F7") (pinfunction "IO/VREF_0_F7") (pintype "bidirectional"))
    )
    (net (code "503") (name "/SWITCH2") (class "Default")
      (node (ref "U1") (pin "C6") (pinfunction "IO_L08N_0_C6") (pintype "bidirectional"))
    )
    (net (code "504") (name "/SWITCH3") (class "Default")
      (node (ref "U1") (pin "D6") (pinfunction "IO_L07P_0_D6") (pintype "bidirectional"))
    )
    (net (code "511") (name "2.5V") (class "Default")
      (node (ref "C1_FP1") (pin "2") (pinfunction "2_2") (pintype "passive"))
    )
    (net (code "512") (name "3.3V") (class "Default")
      (node (ref "Q1_FP1") (pin "4") (pinfunction "VCC_4") (pintype "power_in"))
      (node (ref "R1_FP1") (pin "1") (pinfunction "1_1") (pintype "passive"))
    )
    (net (code "513") (name "GND") (class "Default")
      (node (ref "C2_FP1") (pin "1") (pinfunction "1_1") (pintype "passive"))
      (node (ref "Q1_FP1") (pin "2") (pinfunction "GND_2") (pintype "passive"))
    )
    (net (code "514") (name "Net-(Q1_FP1-OUT)") (class "Default")
      (node (ref "Q1_FP1") (pin "3") (pinfunction "OUT_3") (pintype "output"))
      (node (ref "R2_FP1") (pin "2") (pinfunction "2_2") (pintype "passive"))
    )
    (net (code "515") (name "Vref") (class "Default")
      (node (ref "C1_FP1") (pin "1") (pinfunction "1_1") (pintype "passive"))
      (node (ref "C2_FP1") (pin "2") (pinfunction "2_2") (pintype "passive"))
      (node (ref "U1") (pin "AA2") (pinfunction "IO_L09N_6/VREF_6_AA2") (pintype "bidirectional"))
      (node (ref "U1") (pin "AC2") (pinfunction "IO_L03N_6/VREF_6_AC2") (pintype "bidirectional"))
      (node (ref "U1") (pin "P1") (pinfunction "IO_L40P_6/VREF_6_P1") (pintype "bidirectional"))
      (node (ref "U1") (pin "R2") (pinfunction "IO_L34N_6/VREF_6_R2") (pintype "bidirectional"))
      (node (ref "U1") (pin "U4") (pinfunction "IO_L24N_6/VREF_6_U4") (pintype "bidirectional"))
      (node (ref "U1") (pin "W3") (pinfunction "IO_L17P_6/VREF_6_W3") (pintype "bidirectional"))
    )
    (net (code "516") (name "unconnected-(Q1_FP1-OE-Pad1)") (class "Default")
      (node (ref "Q1_FP1") (pin "1") (pinfunction "OE_1") (pintype "input+no_connect"))
    )
    (net (code "517") (name "unconnected-(U1A-IO-PadAD15)") (class "Default")
      (node (ref "U1") (pin "AD15") (pinfunction "IO_AD15") (pintype "bidirectional+no_connect"))
    )
    (net (code "518") (name "unconnected-(U1A-IO-PadW15)") (class "Default")
      (node (ref "U1") (pin "W15") (pinfunction "IO_W15") (pintype "bidirectional+no_connect"))
    )
    (net (code "519") (name "unconnected-(U1A-IO-PadW16)") (class "Default")
      (node (ref "U1") (pin "W16") (pinfunction "IO_W16") (pintype "bidirectional+no_connect"))
    )
    (net (code "520") (name "unconnected-(U1A-IO_L05N_6-PadAB2)") (class "Default")
      (node (ref "U1") (pin "AB2") (pinfunction "IO_L05N_6_AB2") (pintype "bidirectional+no_connect"))
    )
    (net (code "521") (name "unconnected-(U1A-IO_L05P_6-PadAB1)") (class "Default")
      (node (ref "U1") (pin "AB1") (pinfunction "IO_L05P_6_AB1") (pintype "bidirectional+no_connect"))
    )
    (net (code "522") (name "unconnected-(U1A-IO_L06N_6-PadY7)") (class "Default")
      (node (ref "U1") (pin "Y7") (pinfunction "IO_L06N_6_Y7") (pintype "bidirectional+no_connect"))
    )
    (net (code "523") (name "unconnected-(U1A-IO_L06P_6-PadY6)") (class "Default")
      (node (ref "U1") (pin "Y6") (pinfunction "IO_L06P_6_Y6") (pintype "bidirectional+no_connect"))
    )
    (net (code "524") (name "unconnected-(U1A-IO_L07N_6-PadAA4)") (class "Default")
      (node (ref "U1") (pin "AA4") (pinfunction "IO_L07N_6_AA4") (pintype "bidirectional+no_connect"))
    )
    (net (code "525") (name "unconnected-(U1A-IO_L07P_6-PadAA3)") (class "Default")
      (node (ref "U1") (pin "AA3") (pinfunction "IO_L07P_6_AA3") (pintype "bidirectional+no_connect"))
    )
    (net (code "526") (name "unconnected-(U1A-IO_L08N_6-PadY5)") (class "Default")
      (node (ref "U1") (pin "Y5") (pinfunction "IO_L08N_6_Y5") (pintype "bidirectional+no_connect"))
    )
    (net (code "527") (name "unconnected-(U1A-IO_L08P_6-PadY4)") (class "Default")
      (node (ref "U1") (pin "Y4") (pinfunction "IO_L08P_6_Y4") (pintype "bidirectional+no_connect"))
    )
    (net (code "528") (name "unconnected-(U1A-IO_L09P_6-PadAA1)") (class "Default")
      (node (ref "U1") (pin "AA1") (pinfunction "IO_L09P_6_AA1") (pintype "bidirectional+no_connect"))
    )
    (net (code "529") (name "unconnected-(U1A-IO_L10N_6-PadY2)") (class "Default")
      (node (ref "U1") (pin "Y2") (pinfunction "IO_L10N_6_Y2") (pintype "bidirectional+no_connect"))
    )
    (net (code "530") (name "unconnected-(U1A-IO_L10P_6-PadY1)") (class "Default")
      (node (ref "U1") (pin "Y1") (pinfunction "IO_L10P_6_Y1") (pintype "bidirectional+no_connect"))
    )
    (net (code "531") (name "unconnected-(U1A-IO_L11N_4-PadY19)") (class "Default")
      (node (ref "U1") (pin "Y19") (pinfunction "IO_L11N_4_Y19") (pintype "bidirectional+no_connect"))
    )
    (net (code "532") (name "unconnected-(U1A-IO_L11P_4-PadAA19)") (class "Default")
      (node (ref "U1") (pin "AA19") (pinfunction "IO_L11P_4_AA19") (pintype "bidirectional+no_connect"))
    )
    (net (code "533") (name "unconnected-(U1A-IO_L17P_4-PadAC18)") (class "Default")
      (node (ref "U1") (pin "AC18") (pinfunction "IO_L17P_4_AC18") (pintype "bidirectional+no_connect"))
    )
    (net (code "534") (name "unconnected-(U1A-IO_L18N_4-PadAD18)") (class "Default")
      (node (ref "U1") (pin "AD18") (pinfunction "IO_L18N_4_AD18") (pintype "bidirectional+no_connect"))
    )
    (net (code "535") (name "unconnected-(U1A-IO_L19N_4-PadAC17)") (class "Default")
      (node (ref "U1") (pin "AC17") (pinfunction "IO_L19N_4_AC17") (pintype "bidirectional+no_connect"))
    )
    (net (code "536") (name "unconnected-(U1A-IO_L19P_4-PadAA17)") (class "Default")
      (node (ref "U1") (pin "AA17") (pinfunction "IO_L19P_4_AA17") (pintype "bidirectional+no_connect"))
    )
    (net (code "537") (name "unconnected-(U1A-IO_L22N_4{slash}VREF_4-PadAD17)") (class "Default")
      (node (ref "U1") (pin "AD17") (pinfunction "IO_L22N_4/VREF_4_AD17") (pintype "bidirectional+no_connect"))
    )
    (net (code "538") (name "unconnected-(U1A-IO_L23N_4-PadAE17)") (class "Default")
      (node (ref "U1") (pin "AE17") (pinfunction "IO_L23N_4_AE17") (pintype "bidirectional+no_connect"))
    )
    (net (code "539") (name "unconnected-(U1A-IO_L23P_4-PadAF17)") (class "Default")
      (node (ref "U1") (pin "AF17") (pinfunction "IO_L23P_4_AF17") (pintype "bidirectional+no_connect"))
    )
    (net (code "540") (name "unconnected-(U1A-IO_L24N_4-PadY16)") (class "Default")
      (node (ref "U1") (pin "Y16") (pinfunction "IO_L24N_4_Y16") (pintype "bidirectional+no_connect"))
    )
    (net (code "541") (name "unconnected-(U1A-IO_L24P_4-PadAA16)") (class "Default")
      (node (ref "U1") (pin "AA16") (pinfunction "IO_L24P_4_AA16") (pintype "bidirectional+no_connect"))
    )
    (net (code "542") (name "unconnected-(U1A-IO_L25N_4-PadAB16)") (class "Default")
      (node (ref "U1") (pin "AB16") (pinfunction "IO_L25N_4_AB16") (pintype "bidirectional+no_connect"))
    )
    (net (code "543") (name "unconnected-(U1A-IO_L25P_4-PadAC16)") (class "Default")
      (node (ref "U1") (pin "AC16") (pinfunction "IO_L25P_4_AC16") (pintype "bidirectional+no_connect"))
    )
    (net (code "544") (name "unconnected-(U1A-IO_L26N_4-PadAE16)") (class "Default")
      (node (ref "U1") (pin "AE16") (pinfunction "IO_L26N_4_AE16") (pintype "bidirectional+no_connect"))
    )
    (net (code "545") (name "unconnected-(U1A-IO_L26P_4{slash}VREF_4-PadAF16)") (class "Default")
      (node (ref "U1") (pin "AF16") (pinfunction "IO_L26P_4/VREF_4_AF16") (pintype "bidirectional+no_connect"))
    )
    (net (code "546") (name "unconnected-(U1A-IO_L28N_4-PadAA15)") (class "Default")
      (node (ref "U1") (pin "AA15") (pinfunction "IO_L28N_4_AA15") (pintype "bidirectional+no_connect"))
    )
    (net (code "547") (name "unconnected-(U1A-IO_L28P_4-PadAB15)") (class "Default")
      (node (ref "U1") (pin "AB15") (pinfunction "IO_L28P_4_AB15") (pintype "bidirectional+no_connect"))
    )
    (net (code "548") (name "unconnected-(U1A-IO_L29N_4-PadAE15)") (class "Default")
      (node (ref "U1") (pin "AE15") (pinfunction "IO_L29N_4_AE15") (pintype "bidirectional+no_connect"))
    )
    (net (code "549") (name "unconnected-(U1A-IO_L29P_4-PadAF15)") (class "Default")
      (node (ref "U1") (pin "AF15") (pinfunction "IO_L29P_4_AF15") (pintype "bidirectional+no_connect"))
    )
    (net (code "550") (name "unconnected-(U1A-IO_L32N_0{slash}GCLK7-PadB13)") (class "Default")
      (node (ref "U1") (pin "B13") (pinfunction "IO_L32N_0/GCLK7_B13") (pintype "bidirectional+no_connect"))
    )
    (net (code "551") (name "unconnected-(U1A-IO_L32P_0{slash}GCLK6-PadA13)") (class "Default")
      (node (ref "U1") (pin "A13") (pinfunction "IO_L32P_0/GCLK6_A13") (pintype "bidirectional+no_connect"))
    )
    (net (code "552") (name "unconnected-(U1A-NC-PadAA5)") (class "Default")
      (node (ref "U1") (pin "AA5") (pinfunction "NC_AA5") (pintype "passive+no_connect"))
    )
    (net (code "553") (name "unconnected-(U1A-NC-PadF22)") (class "Default")
      (node (ref "U1") (pin "F22") (pinfunction "NC_F22") (pintype "passive+no_connect"))
    )
  )
)
